# Receiver.net
KiCad netlist of a schematic drawn in Altium Designer
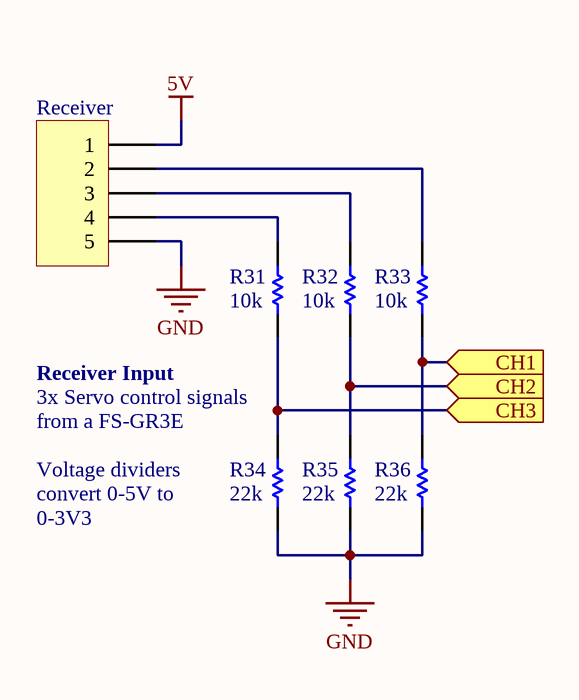
[diagram p0: Receiver.SchDoc]

(export (version "E")
  (design (tool "Eeschema 10.0.6"))
  (components
    (comp (ref "R31")
      (value "10k")
      (footprint "J1-0603")
      (description "Resistor")
      (fields (field (name "Comment") "Res1") (field (name "PUBLISHER") "Altium Limited"))
      (libsource (lib "Miscellaneous Devices") (part "Res1"))
    )
    (comp (ref "R32")
      (value "10k")
      (footprint "J1-0603")
      (description "Resistor")
      (fields (field (name "Comment") "Res1") (field (name "PUBLISHER") "Altium Limited"))
      (libsource (lib "Miscellaneous Devices") (part "Res1"))
    )
    (comp (ref "R33")
      (value "10k")
      (footprint "J1-0603")
      (description "Resistor")
      (fields (field (name "Comment") "Res1") (field (name "PUBLISHER") "Altium Limited"))
      (libsource (lib "Miscellaneous Devices") (part "Res1"))
    )
    (comp (ref "R34")
      (value "22k")
      (footprint "J1-0603")
      (description "Resistor")
      (fields (field (name "Comment") "Res1") (field (name "PUBLISHER") "Altium Limited"))
      (libsource (lib "Miscellaneous Devices") (part "Res1"))
    )
    (comp (ref "R35")
      (value "22k")
      (footprint "J1-0603")
      (description "Resistor")
      (fields (field (name "Comment") "Res1") (field (name "PUBLISHER") "Altium Limited"))
      (libsource (lib "Miscellaneous Devices") (part "Res1"))
    )
    (comp (ref "R36")
      (value "22k")
      (footprint "J1-0603")
      (description "Resistor")
      (fields (field (name "Comment") "Res1") (field (name "PUBLISHER") "Altium Limited"))
      (libsource (lib "Miscellaneous Devices") (part "Res1"))
    )
    (comp (ref "Receiver")
      (value "~")
      (footprint "HDR1X5")
      (description "Receiver Input")
      (fields (field (name "PUBLISHER") "Altium Limited"))
      (libsource (lib "Miscellaneous Connectors") (part "Header 5"))
    )
  )
  (nets
    (net (code "1") (name "/CH1") (class "Default")
      (node (ref "R33") (pin "1") (pinfunction "1_1") (pintype "passive"))
      (node (ref "R36") (pin "2") (pinfunction "2_2") (pintype "passive"))
    )
    (net (code "2") (name "/CH2") (class "Default")
      (node (ref "R32") (pin "1") (pinfunction "1_1") (pintype "passive"))
      (node (ref "R35") (pin "2") (pinfunction "2_2") (pintype "passive"))
    )
    (net (code "3") (name "/CH3") (class "Default")
      (node (ref "R31") (pin "1") (pinfunction "1_1") (pintype "passive"))
      (node (ref "R34") (pin "2") (pinfunction "2_2") (pintype "passive"))
    )
    (net (code "4") (name "5V") (class "Default")
      (node (ref "Receiver") (pin "1") (pinfunction "1_1") (pintype "passive"))
    )
    (net (code "5") (name "GND") (class "Default")
      (node (ref "R34") (pin "1") (pinfunction "1_1") (pintype "passive"))
      (node (ref "R35") (pin "1") (pinfunction "1_1") (pintype "passive"))
      (node (ref "R36") (pin "1") (pinfunction "1_1") (pintype "passive"))
      (node (ref "Receiver") (pin "5") (pinfunction "5_5") (pintype "passive"))
    )
    (net (code "6") (name "Net-(R31-Pad2)") (class "Default")
      (node (ref "R31") (pin "2") (pinfunction "2_2") (pintype "passive"))
      (node (ref "Receiver") (pin "4") (pinfunction "4_4") (pintype "passive"))
    )
    (net (code "7") (name "Net-(R32-Pad2)") (class "Default")
      (node (ref "R32") (pin "2") (pinfunction "2_2") (pintype "passive"))
      (node (ref "Receiver") (pin "3") (pinfunction "3_3") (pintype "passive"))
    )
    (net (code "8") (name "Net-(R33-Pad2)") (class "Default")
      (node (ref "R33") (pin "2") (pinfunction "2_2") (pintype "passive"))
      (node (ref "Receiver") (pin "2") (pinfunction "2_2") (pintype "passive"))
    )
  )
)
